# lononTV.net
KiCad netlist of a schematic drawn in Altium Designer
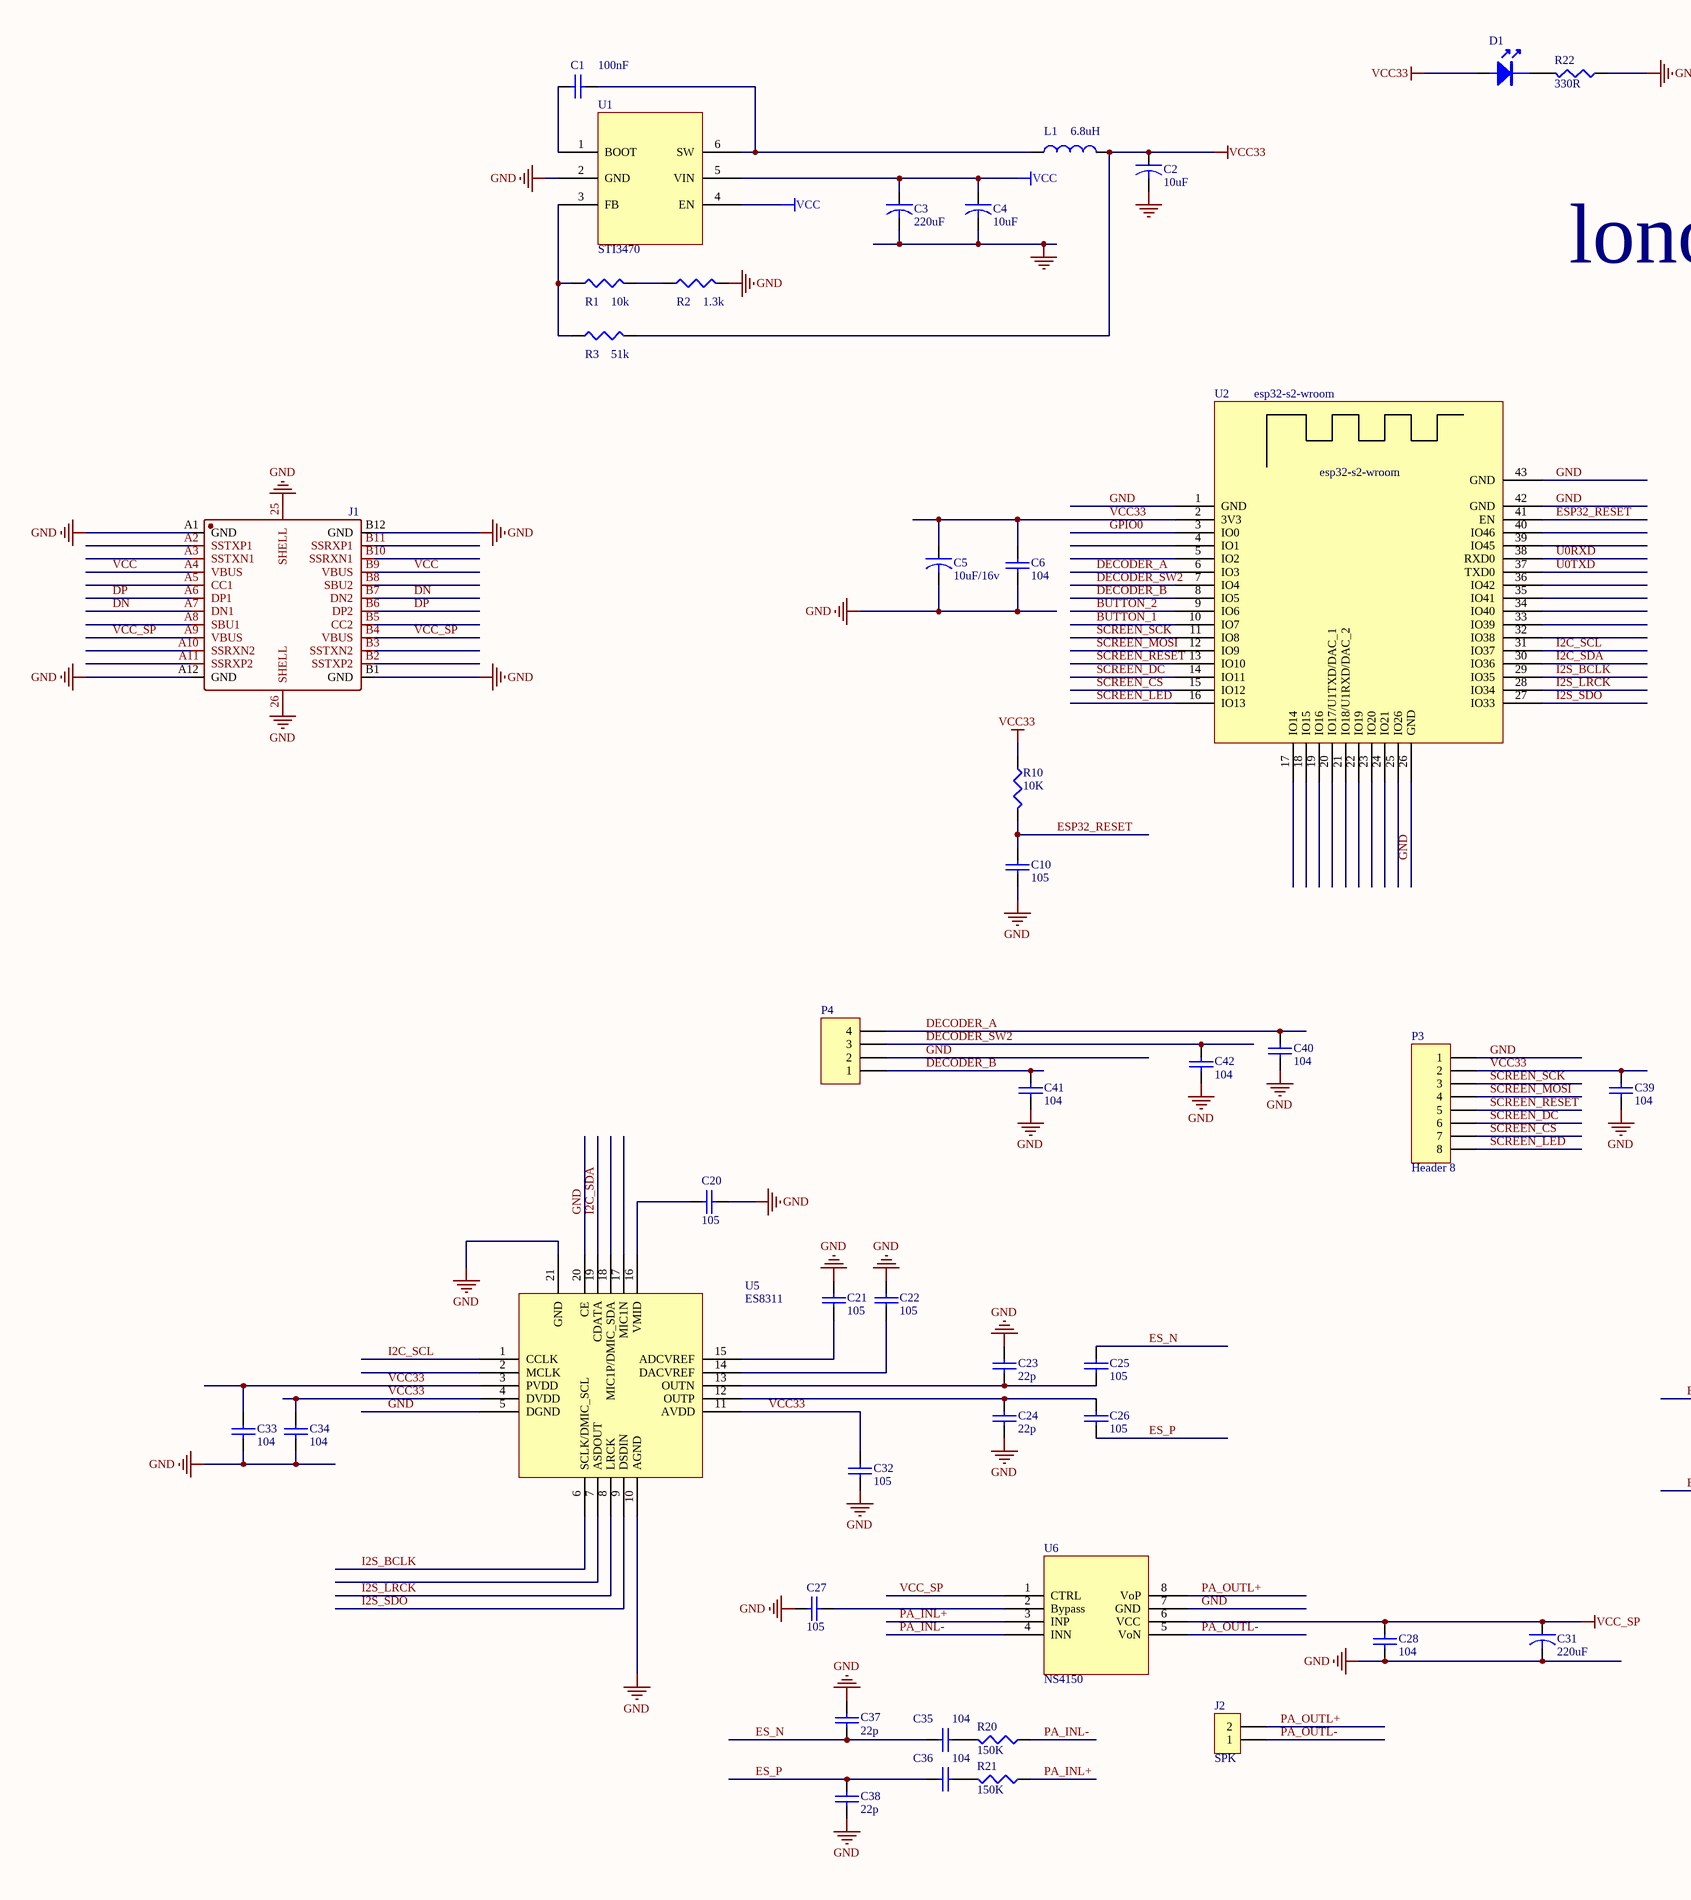
[diagram p0: lononTV.SchDoc, left]
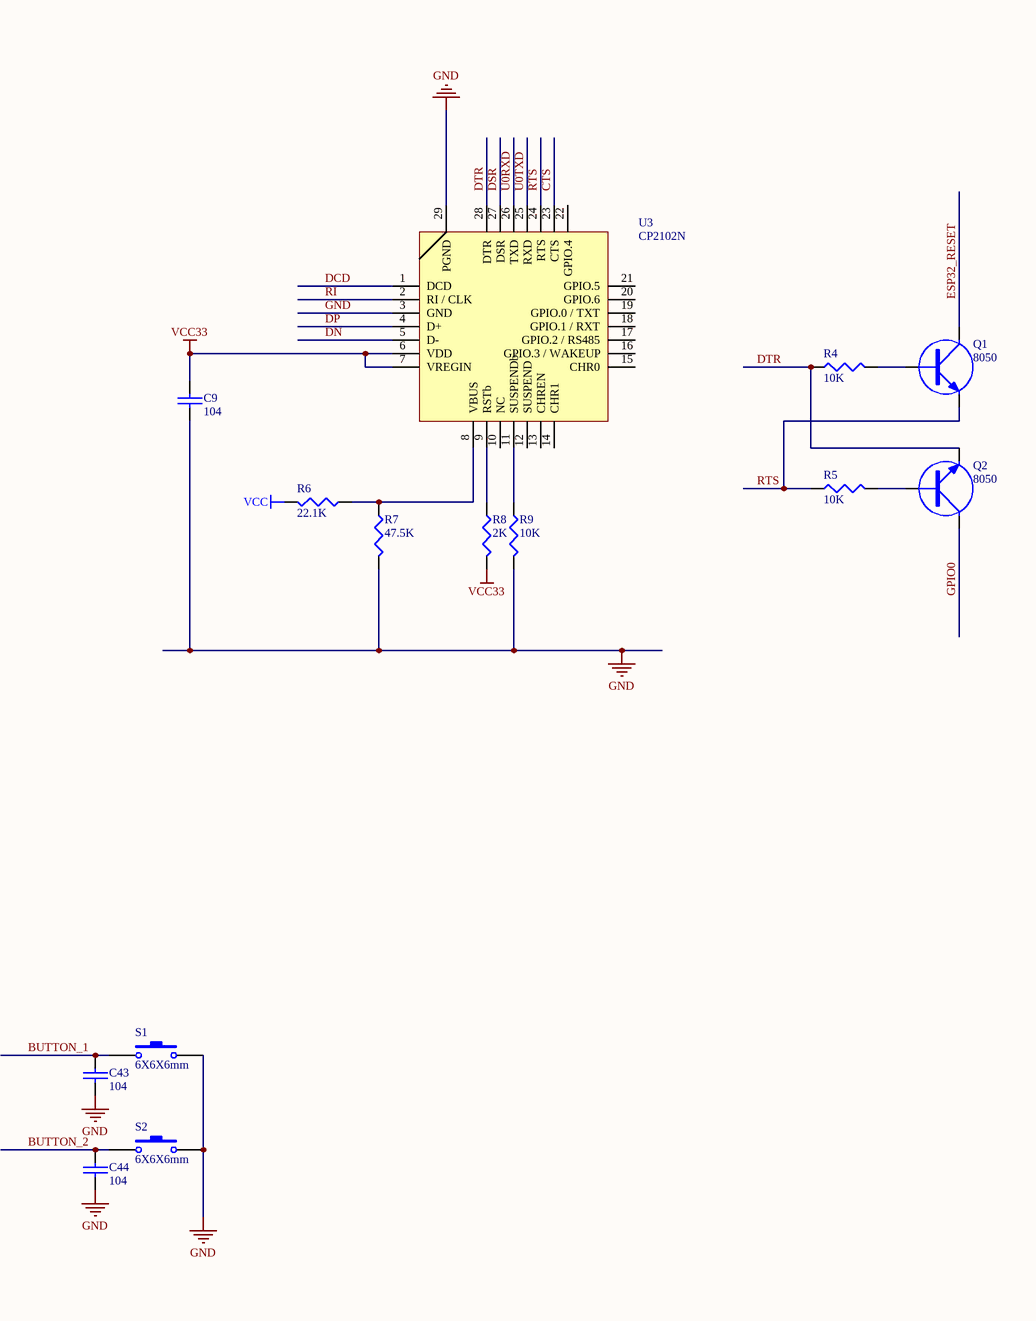
[diagram p1: lononTV.SchDoc, right]

(export (version "E")
  (design (tool "Eeschema 10.0.6"))
  (components
    (comp (ref "C1")
      (value "100nF")
      (footprint "0603C")
      (description "贴片电容")
      (libsource (lib "*") (part "CAP"))
    )
    (comp (ref "C2")
      (value "10uF")
      (footprint "1206-A")
      (description "钽电容")
      (libsource (lib "*") (part "CAPACITOR"))
    )
    (comp (ref "C3")
      (value "220uF")
      (footprint "铝电容6.6")
      (description "钽电容")
      (libsource (lib "*") (part "CAPACITOR"))
    )
    (comp (ref "C4")
      (value "10uF")
      (footprint "1206-A")
      (description "钽电容")
      (libsource (lib "*") (part "CAPACITOR"))
    )
    (comp (ref "C5")
      (value "10uF/16v")
      (footprint "1206-A")
      (description "Capacitor")
      (libsource (lib "zhjrm") (part "CAPACITOR"))
    )
    (comp (ref "C6")
      (value "104")
      (footprint "C0603 - duplicate")
      (description "Capacitor")
      (libsource (lib "zhjrm") (part "CAP"))
    )
    (comp (ref "C9")
      (value "104")
      (footprint "C0603 - duplicate")
      (description "Capacitor")
      (libsource (lib "zhjrm") (part "CAP"))
    )
    (comp (ref "C10")
      (value "105")
      (footprint "C0603 - duplicate")
      (description "Capacitor")
      (libsource (lib "zhjrm") (part "CAP"))
    )
    (comp (ref "C20")
      (value "105")
      (footprint "C0603 - duplicate")
      (description "Capacitor")
      (libsource (lib "zhjrm") (part "CAP"))
    )
    (comp (ref "C21")
      (value "105")
      (footprint "C0603 - duplicate")
      (description "Capacitor")
      (libsource (lib "zhjrm") (part "CAP"))
    )
    (comp (ref "C22")
      (value "105")
      (footprint "C0603 - duplicate")
      (description "Capacitor")
      (libsource (lib "zhjrm") (part "CAP"))
    )
    (comp (ref "C23")
      (value "22p")
      (footprint "C0603 - duplicate")
      (description "Capacitor")
      (libsource (lib "zhjrm") (part "CAP"))
    )
    (comp (ref "C24")
      (value "22p")
      (footprint "C0603 - duplicate")
      (description "Capacitor")
      (libsource (lib "zhjrm") (part "CAP"))
    )
    (comp (ref "C25")
      (value "105")
      (footprint "C0603 - duplicate")
      (description "Capacitor")
      (libsource (lib "zhjrm") (part "CAP"))
    )
    (comp (ref "C26")
      (value "105")
      (footprint "C0603 - duplicate")
      (description "Capacitor")
      (libsource (lib "zhjrm") (part "CAP"))
    )
    (comp (ref "C27")
      (value "105")
      (footprint "C0603 - duplicate")
      (description "Capacitor")
      (libsource (lib "zhjrm") (part "CAP"))
    )
    (comp (ref "C28")
      (value "104")
      (footprint "C0603 - duplicate")
      (description "Capacitor")
      (libsource (lib "zhjrm") (part "CAP"))
    )
    (comp (ref "C31")
      (value "220uF")
      (footprint "铝电容6.6")
      (description "Capacitor")
      (libsource (lib "zhjrm") (part "CAPACITOR"))
    )
    (comp (ref "C32")
      (value "105")
      (footprint "C0603 - duplicate")
      (description "Capacitor")
      (libsource (lib "zhjrm") (part "CAP"))
    )
    (comp (ref "C33")
      (value "104")
      (footprint "C0603 - duplicate")
      (description "Capacitor")
      (libsource (lib "zhjrm") (part "CAP"))
    )
    (comp (ref "C34")
      (value "104")
      (footprint "C0603 - duplicate")
      (description "Capacitor")
      (libsource (lib "zhjrm") (part "CAP"))
    )
    (comp (ref "C35")
      (value "104")
      (footprint "C0603 - duplicate")
      (description "Capacitor")
      (libsource (lib "zhjrm") (part "CAP"))
    )
    (comp (ref "C36")
      (value "104")
      (footprint "C0603 - duplicate")
      (description "Capacitor")
      (libsource (lib "zhjrm") (part "CAP"))
    )
    (comp (ref "C37")
      (value "22p")
      (footprint "C0603 - duplicate")
      (description "Capacitor")
      (libsource (lib "zhjrm") (part "CAP"))
    )
    (comp (ref "C38")
      (value "22p")
      (footprint "C0603 - duplicate")
      (description "Capacitor")
      (libsource (lib "zhjrm") (part "CAP"))
    )
    (comp (ref "C39")
      (value "104")
      (footprint "C0603 - duplicate")
      (description "Capacitor")
      (libsource (lib "zhjrm") (part "CAP"))
    )
    (comp (ref "C40")
      (value "104")
      (footprint "C0603 - duplicate")
      (description "Capacitor")
      (libsource (lib "zhjrm") (part "CAP"))
    )
    (comp (ref "C41")
      (value "104")
      (footprint "C0603 - duplicate")
      (description "Capacitor")
      (libsource (lib "zhjrm") (part "CAP"))
    )
    (comp (ref "C42")
      (value "104")
      (footprint "C0603 - duplicate")
      (description "Capacitor")
      (libsource (lib "zhjrm") (part "CAP"))
    )
    (comp (ref "C43")
      (value "104")
      (footprint "C0603 - duplicate")
      (description "Capacitor")
      (libsource (lib "zhjrm") (part "CAP"))
    )
    (comp (ref "C44")
      (value "104")
      (footprint "C0603 - duplicate")
      (description "Capacitor")
      (libsource (lib "zhjrm") (part "CAP"))
    )
    (comp (ref "D1") (value "~") (footprint "d0805") (libsource (lib "zhjrm") (part "LED")))
    (comp (ref "J1")
      (value "~")
      (footprint "TYPE-C夹板C2856664")
      (libsource (lib "zhjrm") (part "TYPE-C夹板C2856664"))
    )
    (comp (ref "J2") (value "SPK") (footprint "MX1.25-2P 立") (libsource (lib "zhjrm") (part "CON2")))
    (comp (ref "L1")
      (value "6.8uH")
      (footprint "电感7.4*6.6")
      (description "Inductor")
      (fields
        (field (name "MANUFACTURER") "Generic Components")
        (field (name "PUBLISHER") "Altium Hobart Technology Centre")
      )
      (libsource (lib "zhjrm") (part "Inductor"))
    )
    (comp (ref "P3")
      (value "Header 8")
      (footprint "HDR1X8")
      (description "Header, 8-Pin")
      (fields (field (name "PUBLISHER") "Altium Limited"))
      (libsource (lib "Miscellaneous Connectors") (part "Header 8"))
    )
    (comp (ref "P4")
      (value "Header 4")
      (footprint "MX1.25-4P 卧")
      (description "Header, 4-Pin")
      (fields (field (name "PUBLISHER") "Altium Limited"))
      (libsource (lib "Miscellaneous Connectors") (part "Header 4"))
    )
    (comp (ref "Q1")
      (value "8050")
      (footprint "3904")
      (description "NPN Transistor")
      (libsource (lib "zhjrm") (part "NPN"))
    )
    (comp (ref "Q2")
      (value "8050")
      (footprint "3904")
      (description "NPN Transistor")
      (libsource (lib "zhjrm") (part "NPN"))
    )
    (comp (ref "R1") (value "10k") (footprint "0603R") (libsource (lib "*") (part "RES1")))
    (comp (ref "R2") (value "1.3k") (footprint "0603R") (libsource (lib "*") (part "RES1")))
    (comp (ref "R3") (value "51k") (footprint "0603R") (libsource (lib "*") (part "RES1")))
    (comp (ref "R4") (value "10K") (footprint "R0603") (libsource (lib "zhjrm") (part "RES1")))
    (comp (ref "R5") (value "10K") (footprint "R0603") (libsource (lib "zhjrm") (part "RES1")))
    (comp (ref "R6") (value "22.1K") (footprint "R0603") (libsource (lib "zhjrm") (part "RES1")))
    (comp (ref "R7") (value "47.5K") (footprint "R0603") (libsource (lib "zhjrm") (part "RES1")))
    (comp (ref "R8") (value "2K") (footprint "R0603") (libsource (lib "zhjrm") (part "RES1")))
    (comp (ref "R9") (value "10K") (footprint "R0603") (libsource (lib "zhjrm") (part "RES1")))
    (comp (ref "R10") (value "10K") (footprint "0603R") (libsource (lib "zhjrm") (part "RES1")))
    (comp (ref "R20") (value "150K") (footprint "0603R") (libsource (lib "zhjrm") (part "RES1")))
    (comp (ref "R21") (value "150K") (footprint "0603R") (libsource (lib "zhjrm") (part "RES1")))
    (comp (ref "R22") (value "330R") (footprint "0603R") (libsource (lib "zhjrm") (part "RES1")))
    (comp (ref "S1")
      (value "6X6X6mm")
      (footprint "C400237_KT红轴")
      (description "Switch")
      (fields (field (name "PUBLISHER") "Altium Limited"))
      (libsource (lib "zhjrm") (part "SW-PB"))
    )
    (comp (ref "S2")
      (value "6X6X6mm")
      (footprint "C400237_KT红轴")
      (description "Switch")
      (fields (field (name "PUBLISHER") "Altium Limited"))
      (libsource (lib "zhjrm") (part "SW-PB"))
    )
    (comp (ref "U1") (value "STI3470") (footprint "SOT-23-6L") (libsource (lib "zhjrm") (part "RT7285/A")))
    (comp (ref "U2")
      (value "esp32-s2-wroom")
      (footprint "ESP32-S2-WROOM")
      (libsource (lib "zhjrm") (part "esp32-s2-wroom"))
    )
    (comp (ref "U3")
      (value "CP2102N")
      (footprint "QFN 28-pin-05P")
      (libsource (lib "zhjrm") (part "CP2102N"))
    )
    (comp (ref "U5") (value "ES8311") (footprint "QFN20_3*3") (libsource (lib "zhjrm") (part "ES8311")))
    (comp (ref "U6") (value "NS4150") (footprint "MSOP8") (libsource (lib "zhjrm") (part "NS4150")))
  )
  (nets
    (net (code "1") (name "/BUTTON_1") (class "Default")
      (node (ref "C43") (pin "1") (pinfunction "1_1") (pintype "passive"))
      (node (ref "S1") (pin "1") (pinfunction "1_1") (pintype "passive"))
      (node (ref "U2") (pin "10") (pinfunction "IO7_10") (pintype "passive"))
    )
    (net (code "2") (name "/BUTTON_2") (class "Default")
      (node (ref "C44") (pin "1") (pinfunction "1_1") (pintype "passive"))
      (node (ref "S2") (pin "1") (pinfunction "1_1") (pintype "passive"))
      (node (ref "U2") (pin "9") (pinfunction "IO6_9") (pintype "passive"))
    )
    (net (code "3") (name "/CTS") (class "Default")
      (node (ref "U3") (pin "23") (pinfunction "CTS_23") (pintype "passive"))
    )
    (net (code "4") (name "/DCD") (class "Default")
      (node (ref "U3") (pin "1") (pinfunction "DCD_1") (pintype "passive"))
    )
    (net (code "5") (name "/DECODER_A") (class "Default")
      (node (ref "C40") (pin "1") (pinfunction "1_1") (pintype "passive"))
      (node (ref "P4") (pin "4") (pinfunction "4_4") (pintype "passive"))
      (node (ref "U2") (pin "6") (pinfunction "IO3_6") (pintype "passive"))
    )
    (net (code "6") (name "/DECODER_B") (class "Default")
      (node (ref "C41") (pin "1") (pinfunction "1_1") (pintype "passive"))
      (node (ref "P4") (pin "1") (pinfunction "1_1") (pintype "passive"))
      (node (ref "U2") (pin "8") (pinfunction "IO5_8") (pintype "passive"))
    )
    (net (code "7") (name "/DECODER_SW2") (class "Default")
      (node (ref "C42") (pin "1") (pinfunction "1_1") (pintype "passive"))
      (node (ref "P4") (pin "3") (pinfunction "3_3") (pintype "passive"))
      (node (ref "U2") (pin "7") (pinfunction "IO4_7") (pintype "passive"))
    )
    (net (code "8") (name "/DN") (class "Default")
      (node (ref "J1") (pin "A7") (pinfunction "DN1_A7") (pintype "passive"))
      (node (ref "J1") (pin "B7") (pinfunction "DN2_B7") (pintype "passive"))
      (node (ref "U3") (pin "5") (pinfunction "D-_5") (pintype "passive"))
    )
    (net (code "9") (name "/DP") (class "Default")
      (node (ref "J1") (pin "A6") (pinfunction "DP1_A6") (pintype "passive"))
      (node (ref "J1") (pin "B6") (pinfunction "DP2_B6") (pintype "passive"))
      (node (ref "U3") (pin "4") (pinfunction "D+_4") (pintype "passive"))
    )
    (net (code "10") (name "/DSR") (class "Default")
      (node (ref "U3") (pin "27") (pinfunction "DSR_27") (pintype "passive"))
    )
    (net (code "11") (name "/DTR") (class "Default")
      (node (ref "Q2") (pin "3") (pinfunction "E_3") (pintype "passive"))
      (node (ref "R4") (pin "1") (pinfunction "1_1") (pintype "passive"))
      (node (ref "U3") (pin "28") (pinfunction "DTR_28") (pintype "passive"))
    )
    (net (code "12") (name "/ESP32_RESET") (class "Default")
      (node (ref "C10") (pin "1") (pinfunction "1_1") (pintype "passive"))
      (node (ref "Q1") (pin "2") (pinfunction "C_2") (pintype "passive"))
      (node (ref "R10") (pin "2") (pinfunction "2_2") (pintype "passive"))
      (node (ref "U2") (pin "41") (pinfunction "EN_41") (pintype "passive"))
    )
    (net (code "13") (name "/ES_N") (class "Default")
      (node (ref "C25") (pin "1") (pinfunction "1_1") (pintype "passive"))
      (node (ref "C35") (pin "2") (pinfunction "2_2") (pintype "passive"))
      (node (ref "C37") (pin "2") (pinfunction "2_2") (pintype "passive"))
    )
    (net (code "14") (name "/ES_P") (class "Default")
      (node (ref "C26") (pin "2") (pinfunction "2_2") (pintype "passive"))
      (node (ref "C36") (pin "2") (pinfunction "2_2") (pintype "passive"))
      (node (ref "C38") (pin "1") (pinfunction "1_1") (pintype "passive"))
    )
    (net (code "15") (name "/GPIO0") (class "Default")
      (node (ref "Q2") (pin "2") (pinfunction "C_2") (pintype "passive"))
      (node (ref "U2") (pin "3") (pinfunction "IO0_3") (pintype "passive"))
    )
    (net (code "16") (name "/I2C_SCL") (class "Default")
      (node (ref "U2") (pin "31") (pinfunction "IO37_31") (pintype "passive"))
      (node (ref "U5") (pin "1") (pinfunction "CCLK_1") (pintype "passive"))
    )
    (net (code "17") (name "/I2C_SDA") (class "Default")
      (node (ref "U2") (pin "30") (pinfunction "IO36_30") (pintype "passive"))
      (node (ref "U5") (pin "19") (pinfunction "CDATA_19") (pintype "passive"))
    )
    (net (code "18") (name "/I2S_BCLK") (class "Default")
      (node (ref "U2") (pin "29") (pinfunction "IO35_29") (pintype "passive"))
      (node (ref "U5") (pin "6") (pinfunction "SCLK/DMIC_SCL_6") (pintype "passive"))
    )
    (net (code "19") (name "/I2S_LRCK") (class "Default")
      (node (ref "U2") (pin "28") (pinfunction "IO34_28") (pintype "passive"))
      (node (ref "U5") (pin "8") (pinfunction "LRCK_8") (pintype "passive"))
    )
    (net (code "20") (name "/I2S_SDO") (class "Default")
      (node (ref "U2") (pin "27") (pinfunction "IO33_27") (pintype "passive"))
      (node (ref "U5") (pin "9") (pinfunction "DSDIN_9") (pintype "passive"))
    )
    (net (code "21") (name "/PA_INL+") (class "Default")
      (node (ref "R21") (pin "1") (pinfunction "1_1") (pintype "passive"))
      (node (ref "U6") (pin "3") (pinfunction "INP_3") (pintype "passive"))
    )
    (net (code "22") (name "/PA_INL-") (class "Default")
      (node (ref "R20") (pin "1") (pinfunction "1_1") (pintype "passive"))
      (node (ref "U6") (pin "4") (pinfunction "INN_4") (pintype "passive"))
    )
    (net (code "23") (name "/PA_OUTL+") (class "Default")
      (node (ref "J2") (pin "2") (pinfunction "2_2") (pintype "passive"))
      (node (ref "U6") (pin "8") (pinfunction "VoP_8") (pintype "passive"))
    )
    (net (code "24") (name "/PA_OUTL-") (class "Default")
      (node (ref "J2") (pin "1") (pinfunction "1_1") (pintype "passive"))
      (node (ref "U6") (pin "5") (pinfunction "VoN_5") (pintype "passive"))
    )
    (net (code "25") (name "/RI") (class "Default")
      (node (ref "U3") (pin "2") (pinfunction "RI_/_CLK_2") (pintype "passive"))
    )
    (net (code "26") (name "/RTS") (class "Default")
      (node (ref "Q1") (pin "3") (pinfunction "E_3") (pintype "passive"))
      (node (ref "R5") (pin "1") (pinfunction "1_1") (pintype "passive"))
      (node (ref "U3") (pin "24") (pinfunction "RTS_24") (pintype "passive"))
    )
    (net (code "27") (name "/SCREEN_CS") (class "Default")
      (node (ref "P3") (pin "7") (pinfunction "7_7") (pintype "passive"))
      (node (ref "U2") (pin "15") (pinfunction "IO12_15") (pintype "passive"))
    )
    (net (code "28") (name "/SCREEN_DC") (class "Default")
      (node (ref "P3") (pin "6") (pinfunction "6_6") (pintype "passive"))
      (node (ref "U2") (pin "14") (pinfunction "IO11_14") (pintype "passive"))
    )
    (net (code "29") (name "/SCREEN_LED") (class "Default")
      (node (ref "P3") (pin "8") (pinfunction "8_8") (pintype "passive"))
      (node (ref "U2") (pin "16") (pinfunction "IO13_16") (pintype "passive"))
    )
    (net (code "30") (name "/SCREEN_MOSI") (class "Default")
      (node (ref "P3") (pin "4") (pinfunction "4_4") (pintype "passive"))
      (node (ref "U2") (pin "12") (pinfunction "IO9_12") (pintype "passive"))
    )
    (net (code "31") (name "/SCREEN_RESET") (class "Default")
      (node (ref "P3") (pin "5") (pinfunction "5_5") (pintype "passive"))
      (node (ref "U2") (pin "13") (pinfunction "IO10_13") (pintype "passive"))
    )
    (net (code "32") (name "/SCREEN_SCK") (class "Default")
      (node (ref "P3") (pin "3") (pinfunction "3_3") (pintype "passive"))
      (node (ref "U2") (pin "11") (pinfunction "IO8_11") (pintype "passive"))
    )
    (net (code "33") (name "/U0RXD") (class "Default")
      (node (ref "U2") (pin "38") (pinfunction "RXD0_38") (pintype "passive"))
      (node (ref "U3") (pin "26") (pinfunction "TXD_26") (pintype "passive"))
    )
    (net (code "34") (name "/U0TXD") (class "Default")
      (node (ref "U2") (pin "37") (pinfunction "TXD0_37") (pintype "passive"))
      (node (ref "U3") (pin "25") (pinfunction "RXD_25") (pintype "passive"))
    )
    (net (code "35") (name "GND") (class "Default")
      (node (ref "C10") (pin "2") (pinfunction "2_2") (pintype "passive"))
      (node (ref "C2") (pin "2") (pinfunction "2_2") (pintype "passive"))
      (node (ref "C20") (pin "2") (pinfunction "2_2") (pintype "passive"))
      (node (ref "C21") (pin "2") (pinfunction "2_2") (pintype "passive"))
      (node (ref "C22") (pin "2") (pinfunction "2_2") (pintype "passive"))
      (node (ref "C23") (pin "1") (pinfunction "1_1") (pintype "passive"))
      (node (ref "C24") (pin "2") (pinfunction "2_2") (pintype "passive"))
      (node (ref "C27") (pin "1") (pinfunction "1_1") (pintype "passive"))
      (node (ref "C28") (pin "1") (pinfunction "1_1") (pintype "passive"))
      (node (ref "C3") (pin "2") (pinfunction "2_2") (pintype "passive"))
      (node (ref "C31") (pin "2") (pinfunction "2_2") (pintype "passive"))
      (node (ref "C32") (pin "1") (pinfunction "1_1") (pintype "passive"))
      (node (ref "C33") (pin "1") (pinfunction "1_1") (pintype "passive"))
      (node (ref "C34") (pin "1") (pinfunction "1_1") (pintype "passive"))
      (node (ref "C37") (pin "1") (pinfunction "1_1") (pintype "passive"))
      (node (ref "C38") (pin "2") (pinfunction "2_2") (pintype "passive"))
      (node (ref "C39") (pin "2") (pinfunction "2_2") (pintype "passive"))
      (node (ref "C4") (pin "2") (pinfunction "2_2") (pintype "passive"))
      (node (ref "C40") (pin "2") (pinfunction "2_2") (pintype "passive"))
      (node (ref "C41") (pin "2") (pinfunction "2_2") (pintype "passive"))
      (node (ref "C42") (pin "2") (pinfunction "2_2") (pintype "passive"))
      (node (ref "C43") (pin "2") (pinfunction "2_2") (pintype "passive"))
      (node (ref "C44") (pin "2") (pinfunction "2_2") (pintype "passive"))
      (node (ref "C5") (pin "2") (pinfunction "2_2") (pintype "passive"))
      (node (ref "C6") (pin "2") (pinfunction "2_2") (pintype "passive"))
      (node (ref "C9") (pin "2") (pinfunction "2_2") (pintype "passive"))
      (node (ref "J1") (pin "25") (pinfunction "SHELL_25") (pintype "passive"))
      (node (ref "J1") (pin "26") (pinfunction "SHELL_26") (pintype "passive"))
      (node (ref "J1") (pin "A1") (pinfunction "GND_A1") (pintype "passive"))
      (node (ref "J1") (pin "A12") (pinfunction "GND_A12") (pintype "passive"))
      (node (ref "J1") (pin "B1") (pinfunction "GND_B1") (pintype "passive"))
      (node (ref "J1") (pin "B12") (pinfunction "GND_B12") (pintype "passive"))
      (node (ref "P3") (pin "1") (pinfunction "1_1") (pintype "passive"))
      (node (ref "P4") (pin "2") (pinfunction "2_2") (pintype "passive"))
      (node (ref "R2") (pin "1") (pinfunction "1_1") (pintype "passive"))
      (node (ref "R22") (pin "1") (pinfunction "1_1") (pintype "passive"))
      (node (ref "R7") (pin "2") (pinfunction "2_2") (pintype "passive"))
      (node (ref "R9") (pin "2") (pinfunction "2_2") (pintype "passive"))
      (node (ref "S1") (pin "2") (pinfunction "2_2") (pintype "passive"))
      (node (ref "S2") (pin "2") (pinfunction "2_2") (pintype "passive"))
      (node (ref "U1") (pin "2") (pinfunction "GND_2") (pintype "passive"))
      (node (ref "U2") (pin "1") (pinfunction "GND_1") (pintype "passive"))
      (node (ref "U2") (pin "26") (pinfunction "GND_26") (pintype "passive"))
      (node (ref "U2") (pin "42") (pinfunction "GND_42") (pintype "passive"))
      (node (ref "U2") (pin "43") (pinfunction "GND_43") (pintype "passive"))
      (node (ref "U3") (pin "29") (pinfunction "PGND_29") (pintype "passive"))
      (node (ref "U3") (pin "3") (pinfunction "GND_3") (pintype "passive"))
      (node (ref "U5") (pin "10") (pinfunction "AGND_10") (pintype "passive"))
      (node (ref "U5") (pin "20") (pinfunction "CE_20") (pintype "passive"))
      (node (ref "U5") (pin "21") (pinfunction "GND_21") (pintype "passive"))
      (node (ref "U5") (pin "5") (pinfunction "DGND_5") (pintype "passive"))
      (node (ref "U6") (pin "7") (pinfunction "GND_7") (pintype "passive"))
    )
    (net (code "36") (name "Net-(C35-Pad1)") (class "Default")
      (node (ref "C35") (pin "1") (pinfunction "1_1") (pintype "passive"))
      (node (ref "R20") (pin "2") (pinfunction "2_2") (pintype "passive"))
    )
    (net (code "37") (name "Net-(C36-Pad1)") (class "Default")
      (node (ref "C36") (pin "1") (pinfunction "1_1") (pintype "passive"))
      (node (ref "R21") (pin "2") (pinfunction "2_2") (pintype "passive"))
    )
    (net (code "38") (name "Net-(D1-2)") (class "Default")
      (node (ref "D1") (pin "K") (pinfunction "2_K") (pintype "passive"))
      (node (ref "R22") (pin "2") (pinfunction "2_2") (pintype "passive"))
    )
    (net (code "39") (name "Net-(Q1-B)") (class "Default")
      (node (ref "Q1") (pin "1") (pinfunction "B_1") (pintype "passive"))
      (node (ref "R4") (pin "2") (pinfunction "2_2") (pintype "passive"))
    )
    (net (code "40") (name "Net-(Q2-B)") (class "Default")
      (node (ref "Q2") (pin "1") (pinfunction "B_1") (pintype "passive"))
      (node (ref "R5") (pin "2") (pinfunction "2_2") (pintype "passive"))
    )
    (net (code "41") (name "Net-(R1-Pad1)") (class "Default")
      (node (ref "R1") (pin "1") (pinfunction "1_1") (pintype "passive"))
      (node (ref "R2") (pin "2") (pinfunction "2_2") (pintype "passive"))
    )
    (net (code "42") (name "Net-(U1-BOOT)") (class "Default")
      (node (ref "C1") (pin "1") (pinfunction "1_1") (pintype "passive"))
      (node (ref "U1") (pin "1") (pinfunction "BOOT_1") (pintype "passive"))
    )
    (net (code "43") (name "Net-(U1-FB)") (class "Default")
      (node (ref "R1") (pin "2") (pinfunction "2_2") (pintype "passive"))
      (node (ref "R3") (pin "2") (pinfunction "2_2") (pintype "passive"))
      (node (ref "U1") (pin "3") (pinfunction "FB_3") (pintype "passive"))
    )
    (net (code "44") (name "Net-(U1-SW)") (class "Default")
      (node (ref "C1") (pin "2") (pinfunction "2_2") (pintype "passive"))
      (node (ref "L1") (pin "1") (pinfunction "1_1") (pintype "passive"))
      (node (ref "U1") (pin "6") (pinfunction "SW_6") (pintype "passive"))
    )
    (net (code "45") (name "Net-(U3-RSTb)") (class "Default")
      (node (ref "R8") (pin "1") (pinfunction "1_1") (pintype "passive"))
      (node (ref "U3") (pin "9") (pinfunction "RSTb_9") (pintype "passive"))
    )
    (net (code "46") (name "Net-(U3-SUSPENDb)") (class "Default")
      (node (ref "R9") (pin "1") (pinfunction "1_1") (pintype "passive"))
      (node (ref "U3") (pin "11") (pinfunction "SUSPENDb_11") (pintype "passive"))
    )
    (net (code "47") (name "Net-(U3-VBUS)") (class "Default")
      (node (ref "R6") (pin "1") (pinfunction "1_1") (pintype "passive"))
      (node (ref "R7") (pin "1") (pinfunction "1_1") (pintype "passive"))
      (node (ref "U3") (pin "8") (pinfunction "VBUS_8") (pintype "passive"))
    )
    (net (code "48") (name "Net-(U5-ADCVREF)") (class "Default")
      (node (ref "C21") (pin "1") (pinfunction "1_1") (pintype "passive"))
      (node (ref "U5") (pin "15") (pinfunction "ADCVREF_15") (pintype "passive"))
    )
    (net (code "49") (name "Net-(U5-DACVREF)") (class "Default")
      (node (ref "C22") (pin "1") (pinfunction "1_1") (pintype "passive"))
      (node (ref "U5") (pin "14") (pinfunction "DACVREF_14") (pintype "passive"))
    )
    (net (code "50") (name "Net-(U5-OUTN)") (class "Default")
      (node (ref "C23") (pin "2") (pinfunction "2_2") (pintype "passive"))
      (node (ref "C25") (pin "2") (pinfunction "2_2") (pintype "passive"))
      (node (ref "U5") (pin "13") (pinfunction "OUTN_13") (pintype "passive"))
    )
    (net (code "51") (name "Net-(U5-OUTP)") (class "Default")
      (node (ref "C24") (pin "1") (pinfunction "1_1") (pintype "passive"))
      (node (ref "C26") (pin "1") (pinfunction "1_1") (pintype "passive"))
      (node (ref "U5") (pin "12") (pinfunction "OUTP_12") (pintype "passive"))
    )
    (net (code "52") (name "Net-(U5-VMID)") (class "Default")
      (node (ref "C20") (pin "1") (pinfunction "1_1") (pintype "passive"))
      (node (ref "U5") (pin "16") (pinfunction "VMID_16") (pintype "passive"))
    )
    (net (code "53") (name "Net-(U6-Bypass)") (class "Default")
      (node (ref "C27") (pin "2") (pinfunction "2_2") (pintype "passive"))
      (node (ref "U6") (pin "2") (pinfunction "Bypass_2") (pintype "passive"))
    )
    (net (code "54") (name "VCC") (class "Default")
      (node (ref "C3") (pin "1") (pinfunction "1_1") (pintype "passive"))
      (node (ref "C4") (pin "1") (pinfunction "1_1") (pintype "passive"))
      (node (ref "J1") (pin "A4") (pinfunction "VBUS_A4") (pintype "passive"))
      (node (ref "J1") (pin "B9") (pinfunction "VBUS_B9") (pintype "passive"))
      (node (ref "R6") (pin "2") (pinfunction "2_2") (pintype "passive"))
      (node (ref "U1") (pin "4") (pinfunction "EN_4") (pintype "passive"))
      (node (ref "U1") (pin "5") (pinfunction "VIN_5") (pintype "passive"))
    )
    (net (code "55") (name "VCC33") (class "Default")
      (node (ref "C2") (pin "1") (pinfunction "1_1") (pintype "passive"))
      (node (ref "C32") (pin "2") (pinfunction "2_2") (pintype "passive"))
      (node (ref "C33") (pin "2") (pinfunction "2_2") (pintype "passive"))
      (node (ref "C34") (pin "2") (pinfunction "2_2") (pintype "passive"))
      (node (ref "C39") (pin "1") (pinfunction "1_1") (pintype "passive"))
      (node (ref "C5") (pin "1") (pinfunction "1_1") (pintype "passive"))
      (node (ref "C6") (pin "1") (pinfunction "1_1") (pintype "passive"))
      (node (ref "C9") (pin "1") (pinfunction "1_1") (pintype "passive"))
      (node (ref "D1") (pin "A") (pinfunction "1_A") (pintype "passive"))
      (node (ref "L1") (pin "2") (pinfunction "2_2") (pintype "passive"))
      (node (ref "P3") (pin "2") (pinfunction "2_2") (pintype "passive"))
      (node (ref "R10") (pin "1") (pinfunction "1_1") (pintype "passive"))
      (node (ref "R3") (pin "1") (pinfunction "1_1") (pintype "passive"))
      (node (ref "R8") (pin "2") (pinfunction "2_2") (pintype "passive"))
      (node (ref "U2") (pin "2") (pinfunction "3V3_2") (pintype "passive"))
      (node (ref "U3") (pin "6") (pinfunction "VDD_6") (pintype "passive"))
      (node (ref "U3") (pin "7") (pinfunction "VREGIN_7") (pintype "passive"))
      (node (ref "U5") (pin "11") (pinfunction "AVDD_11") (pintype "passive"))
      (node (ref "U5") (pin "3") (pinfunction "PVDD_3") (pintype "passive"))
      (node (ref "U5") (pin "4") (pinfunction "DVDD_4") (pintype "passive"))
    )
    (net (code "56") (name "VCC_SP") (class "Default")
      (node (ref "C28") (pin "2") (pinfunction "2_2") (pintype "passive"))
      (node (ref "C31") (pin "1") (pinfunction "1_1") (pintype "passive"))
      (node (ref "J1") (pin "A9") (pinfunction "VBUS_A9") (pintype "passive"))
      (node (ref "J1") (pin "B4") (pinfunction "VBUS_B4") (pintype "passive"))
      (node (ref "U6") (pin "1") (pinfunction "CTRL_1") (pintype "passive"))
      (node (ref "U6") (pin "6") (pinfunction "VCC_6") (pintype "passive"))
    )
    (net (code "57") (name "unconnected-(J1-CC1-PadA5)") (class "Default")
      (node (ref "J1") (pin "A5") (pinfunction "CC1_A5") (pintype "passive"))
    )
    (net (code "58") (name "unconnected-(J1-CC2-PadB5)") (class "Default")
      (node (ref "J1") (pin "B5") (pinfunction "CC2_B5") (pintype "passive"))
    )
    (net (code "59") (name "unconnected-(J1-SBU1-PadA8)") (class "Default")
      (node (ref "J1") (pin "A8") (pinfunction "SBU1_A8") (pintype "passive"))
    )
    (net (code "60") (name "unconnected-(J1-SBU2-PadB8)") (class "Default")
      (node (ref "J1") (pin "B8") (pinfunction "SBU2_B8") (pintype "passive"))
    )
    (net (code "61") (name "unconnected-(J1-SSRXN1-PadB10)") (class "Default")
      (node (ref "J1") (pin "B10") (pinfunction "SSRXN1_B10") (pintype "passive"))
    )
    (net (code "62") (name "unconnected-(J1-SSRXN2-PadA10)") (class "Default")
      (node (ref "J1") (pin "A10") (pinfunction "SSRXN2_A10") (pintype "passive"))
    )
    (net (code "63") (name "unconnected-(J1-SSRXP1-PadB11)") (class "Default")
      (node (ref "J1") (pin "B11") (pinfunction "SSRXP1_B11") (pintype "passive"))
    )
    (net (code "64") (name "unconnected-(J1-SSRXP2-PadA11)") (class "Default")
      (node (ref "J1") (pin "A11") (pinfunction "SSRXP2_A11") (pintype "passive"))
    )
    (net (code "65") (name "unconnected-(J1-SSTXN1-PadA3)") (class "Default")
      (node (ref "J1") (pin "A3") (pinfunction "SSTXN1_A3") (pintype "passive"))
    )
    (net (code "66") (name "unconnected-(J1-SSTXN2-PadB3)") (class "Default")
      (node (ref "J1") (pin "B3") (pinfunction "SSTXN2_B3") (pintype "passive"))
    )
    (net (code "67") (name "unconnected-(J1-SSTXP1-PadA2)") (class "Default")
      (node (ref "J1") (pin "A2") (pinfunction "SSTXP1_A2") (pintype "passive"))
    )
    (net (code "68") (name "unconnected-(J1-SSTXP2-PadB2)") (class "Default")
      (node (ref "J1") (pin "B2") (pinfunction "SSTXP2_B2") (pintype "passive"))
    )
    (net (code "69") (name "unconnected-(U2-IO1-Pad4)") (class "Default")
      (node (ref "U2") (pin "4") (pinfunction "IO1_4") (pintype "passive"))
    )
    (net (code "70") (name "unconnected-(U2-IO2-Pad5)") (class "Default")
      (node (ref "U2") (pin "5") (pinfunction "IO2_5") (pintype "passive"))
    )
    (net (code "71") (name "unconnected-(U2-IO14-Pad17)") (class "Default")
      (node (ref "U2") (pin "17") (pinfunction "IO14_17") (pintype "passive"))
    )
    (net (code "72") (name "unconnected-(U2-IO15-Pad18)") (class "Default")
      (node (ref "U2") (pin "18") (pinfunction "IO15_18") (pintype "passive"))
    )
    (net (code "73") (name "unconnected-(U2-IO16-Pad19)") (class "Default")
      (node (ref "U2") (pin "19") (pinfunction "IO16_19") (pintype "passive"))
    )
    (net (code "74") (name "unconnected-(U2-IO17{slash}U1TXD{slash}DAC_1-Pad20)") (class "Default")
      (node (ref "U2") (pin "20") (pinfunction "IO17/U1TXD/DAC_1_20") (pintype "passive"))
    )
    (net (code "75") (name "unconnected-(U2-IO18{slash}U1RXD{slash}DAC_2-Pad21)") (class "Default")
      (node (ref "U2") (pin "21") (pinfunction "IO18/U1RXD/DAC_2_21") (pintype "passive"))
    )
    (net (code "76") (name "unconnected-(U2-IO19-Pad22)") (class "Default")
      (node (ref "U2") (pin "22") (pinfunction "IO19_22") (pintype "passive"))
    )
    (net (code "77") (name "unconnected-(U2-IO20-Pad23)") (class "Default")
      (node (ref "U2") (pin "23") (pinfunction "IO20_23") (pintype "passive"))
    )
    (net (code "78") (name "unconnected-(U2-IO21-Pad24)") (class "Default")
      (node (ref "U2") (pin "24") (pinfunction "IO21_24") (pintype "passive"))
    )
    (net (code "79") (name "unconnected-(U2-IO26-Pad25)") (class "Default")
      (node (ref "U2") (pin "25") (pinfunction "IO26_25") (pintype "passive"))
    )
    (net (code "80") (name "unconnected-(U2-IO38-Pad32)") (class "Default")
      (node (ref "U2") (pin "32") (pinfunction "IO38_32") (pintype "passive"))
    )
    (net (code "81") (name "unconnected-(U2-IO39-Pad33)") (class "Default")
      (node (ref "U2") (pin "33") (pinfunction "IO39_33") (pintype "passive"))
    )
    (net (code "82") (name "unconnected-(U2-IO40-Pad34)") (class "Default")
      (node (ref "U2") (pin "34") (pinfunction "IO40_34") (pintype "passive"))
    )
    (net (code "83") (name "unconnected-(U2-IO41-Pad35)") (class "Default")
      (node (ref "U2") (pin "35") (pinfunction "IO41_35") (pintype "passive"))
    )
    (net (code "84") (name "unconnected-(U2-IO42-Pad36)") (class "Default")
      (node (ref "U2") (pin "36") (pinfunction "IO42_36") (pintype "passive"))
    )
    (net (code "85") (name "unconnected-(U2-IO45-Pad39)") (class "Default")
      (node (ref "U2") (pin "39") (pinfunction "IO45_39") (pintype "passive"))
    )
    (net (code "86") (name "unconnected-(U2-IO46-Pad40)") (class "Default")
      (node (ref "U2") (pin "40") (pinfunction "IO46_40") (pintype "passive"))
    )
    (net (code "87") (name "unconnected-(U3-CHR0-Pad15)") (class "Default")
      (node (ref "U3") (pin "15") (pinfunction "CHR0_15") (pintype "passive"))
    )
    (net (code "88") (name "unconnected-(U3-CHR1-Pad14)") (class "Default")
      (node (ref "U3") (pin "14") (pinfunction "CHR1_14") (pintype "passive"))
    )
    (net (code "89") (name "unconnected-(U3-CHREN-Pad13)") (class "Default")
      (node (ref "U3") (pin "13") (pinfunction "CHREN_13") (pintype "passive"))
    )
    (net (code "90") (name "unconnected-(U3-GPIO.0_{slash}_TXT-Pad19)") (class "Default")
      (node (ref "U3") (pin "19") (pinfunction "GPIO.0_/_TXT_19") (pintype "passive"))
    )
    (net (code "91") (name "unconnected-(U3-GPIO.1_{slash}_RXT-Pad18)") (class "Default")
      (node (ref "U3") (pin "18") (pinfunction "GPIO.1_/_RXT_18") (pintype "passive"))
    )
    (net (code "92") (name "unconnected-(U3-GPIO.2_{slash}_RS485-Pad17)") (class "Default")
      (node (ref "U3") (pin "17") (pinfunction "GPIO.2_/_RS485_17") (pintype "passive"))
    )
    (net (code "93") (name "unconnected-(U3-GPIO.3_{slash}_WAKEUP-Pad16)") (class "Default")
      (node (ref "U3") (pin "16") (pinfunction "GPIO.3_/_WAKEUP_16") (pintype "passive"))
    )
    (net (code "94") (name "unconnected-(U3-GPIO.4-Pad22)") (class "Default")
      (node (ref "U3") (pin "22") (pinfunction "GPIO.4_22") (pintype "passive"))
    )
    (net (code "95") (name "unconnected-(U3-GPIO.5-Pad21)") (class "Default")
      (node (ref "U3") (pin "21") (pinfunction "GPIO.5_21") (pintype "passive"))
    )
    (net (code "96") (name "unconnected-(U3-GPIO.6-Pad20)") (class "Default")
      (node (ref "U3") (pin "20") (pinfunction "GPIO.6_20") (pintype "passive"))
    )
    (net (code "97") (name "unconnected-(U3-NC-Pad10)") (class "Default")
      (node (ref "U3") (pin "10") (pinfunction "NC_10") (pintype "passive"))
    )
    (net (code "98") (name "unconnected-(U3-SUSPEND-Pad12)") (class "Default")
      (node (ref "U3") (pin "12") (pinfunction "SUSPEND_12") (pintype "passive"))
    )
    (net (code "99") (name "unconnected-(U5-ASDOUT-Pad7)") (class "Default")
      (node (ref "U5") (pin "7") (pinfunction "ASDOUT_7") (pintype "passive"))
    )
    (net (code "100") (name "unconnected-(U5-MCLK-Pad2)") (class "Default")
      (node (ref "U5") (pin "2") (pinfunction "MCLK_2") (pintype "passive"))
    )
    (net (code "101") (name "unconnected-(U5-MIC1N-Pad17)") (class "Default")
      (node (ref "U5") (pin "17") (pinfunction "MIC1N_17") (pintype "passive"))
    )
    (net (code "102") (name "unconnected-(U5-MIC1P{slash}DMIC_SDA-Pad18)") (class "Default")
      (node (ref "U5") (pin "18") (pinfunction "MIC1P/DMIC_SDA_18") (pintype "passive"))
    )
  )
)
